# EEG_Preprocessing.net
KiCad netlist of a schematic drawn in Altium Designer
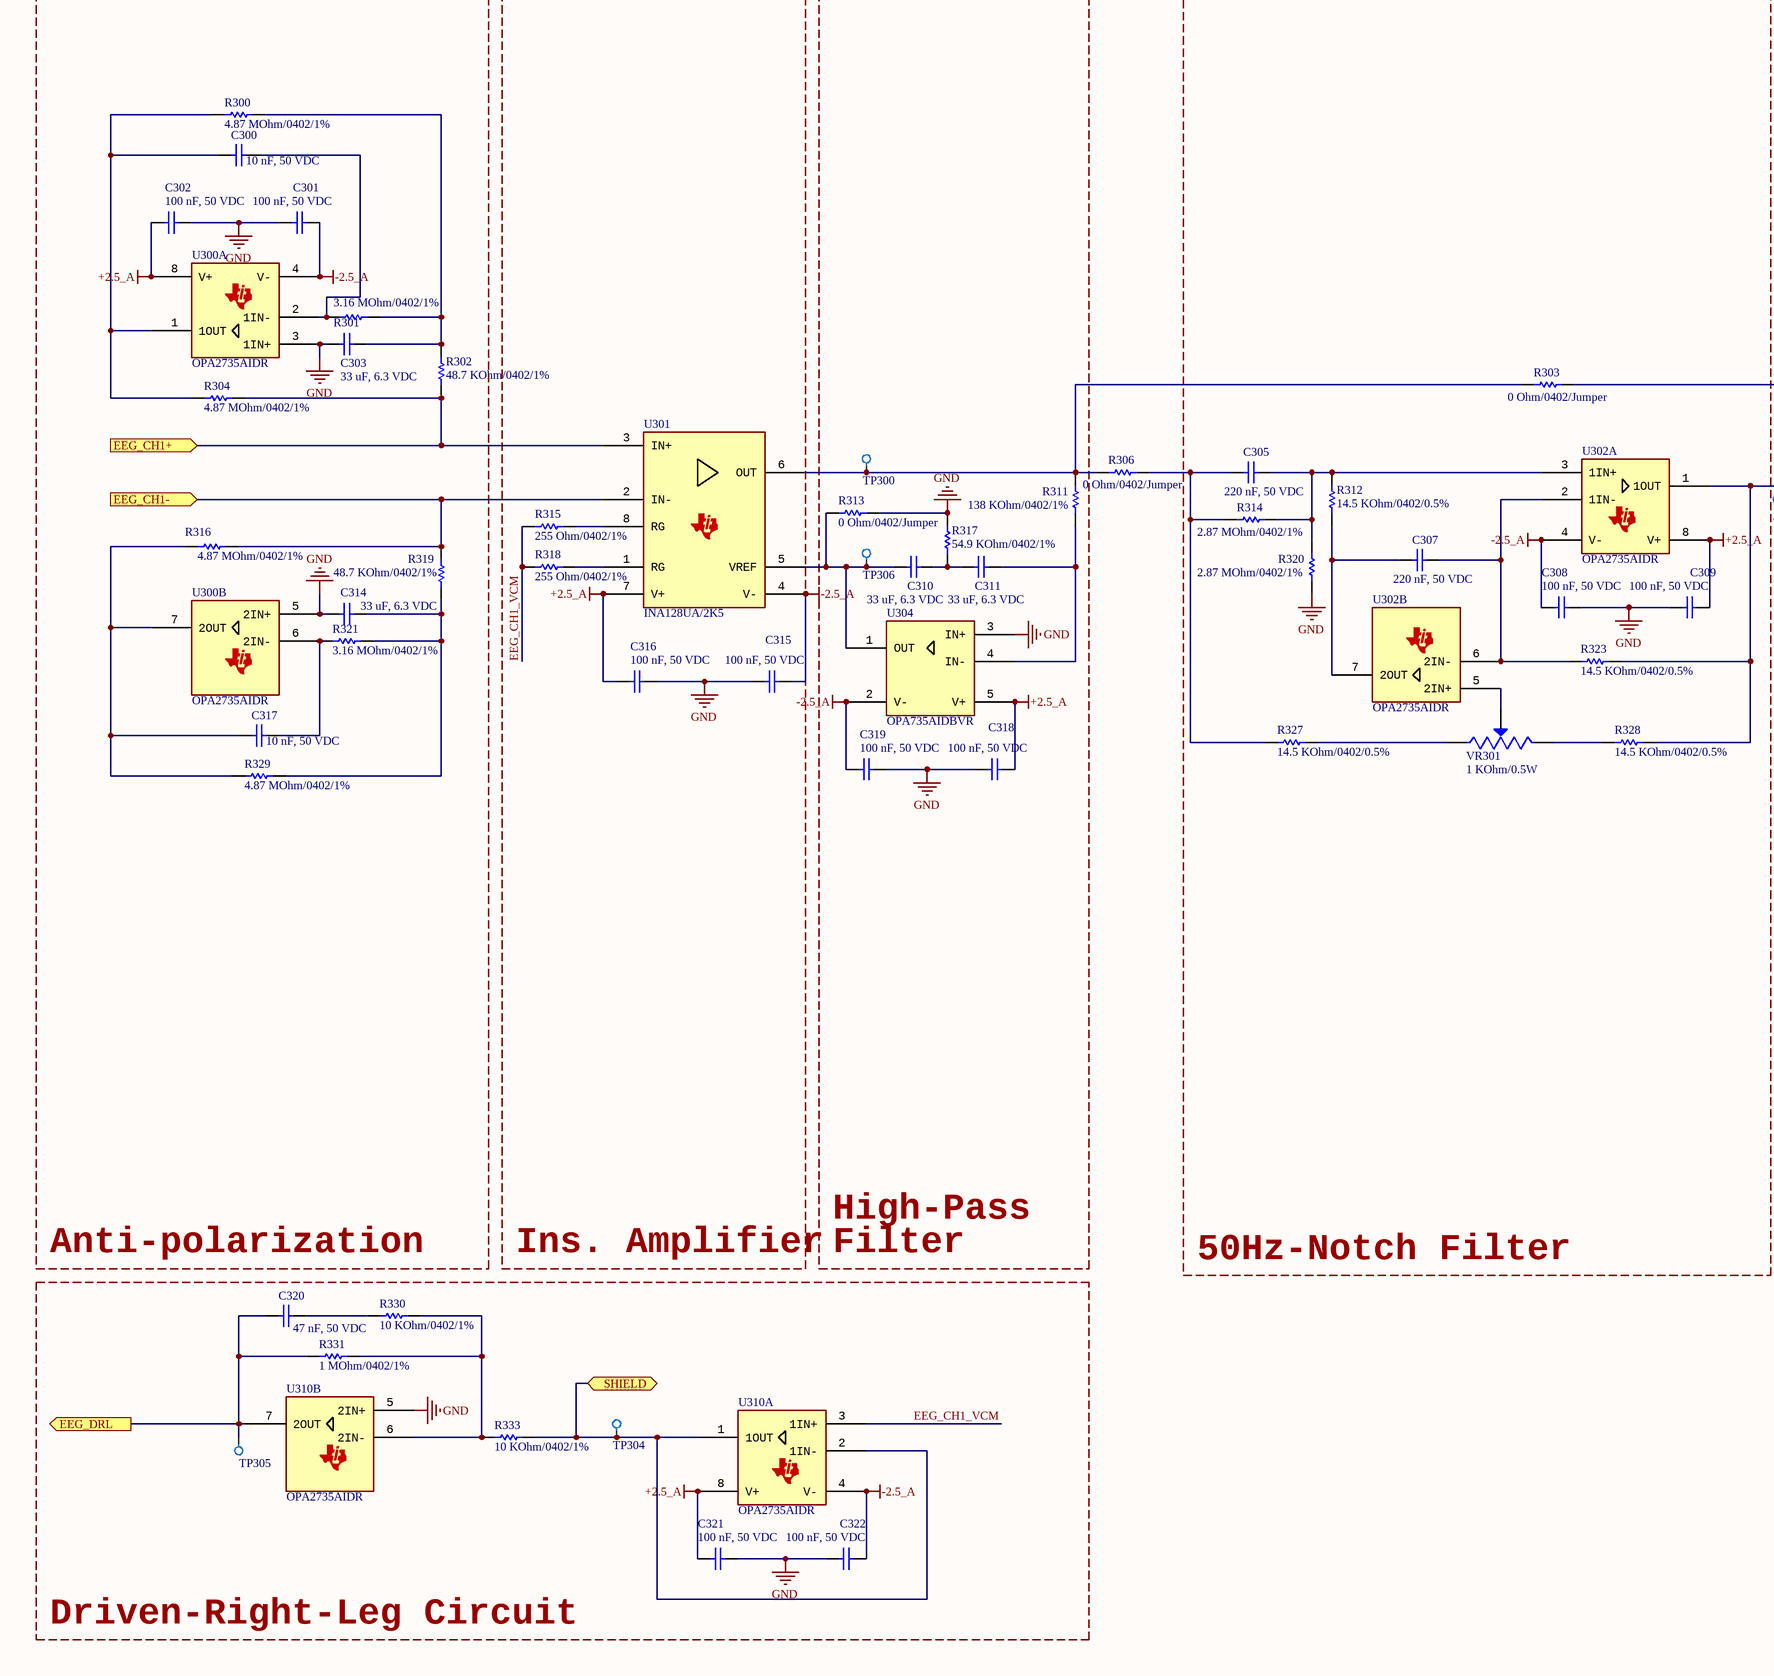
[diagram p0: EEG Preprocessing.SchDoc, left]
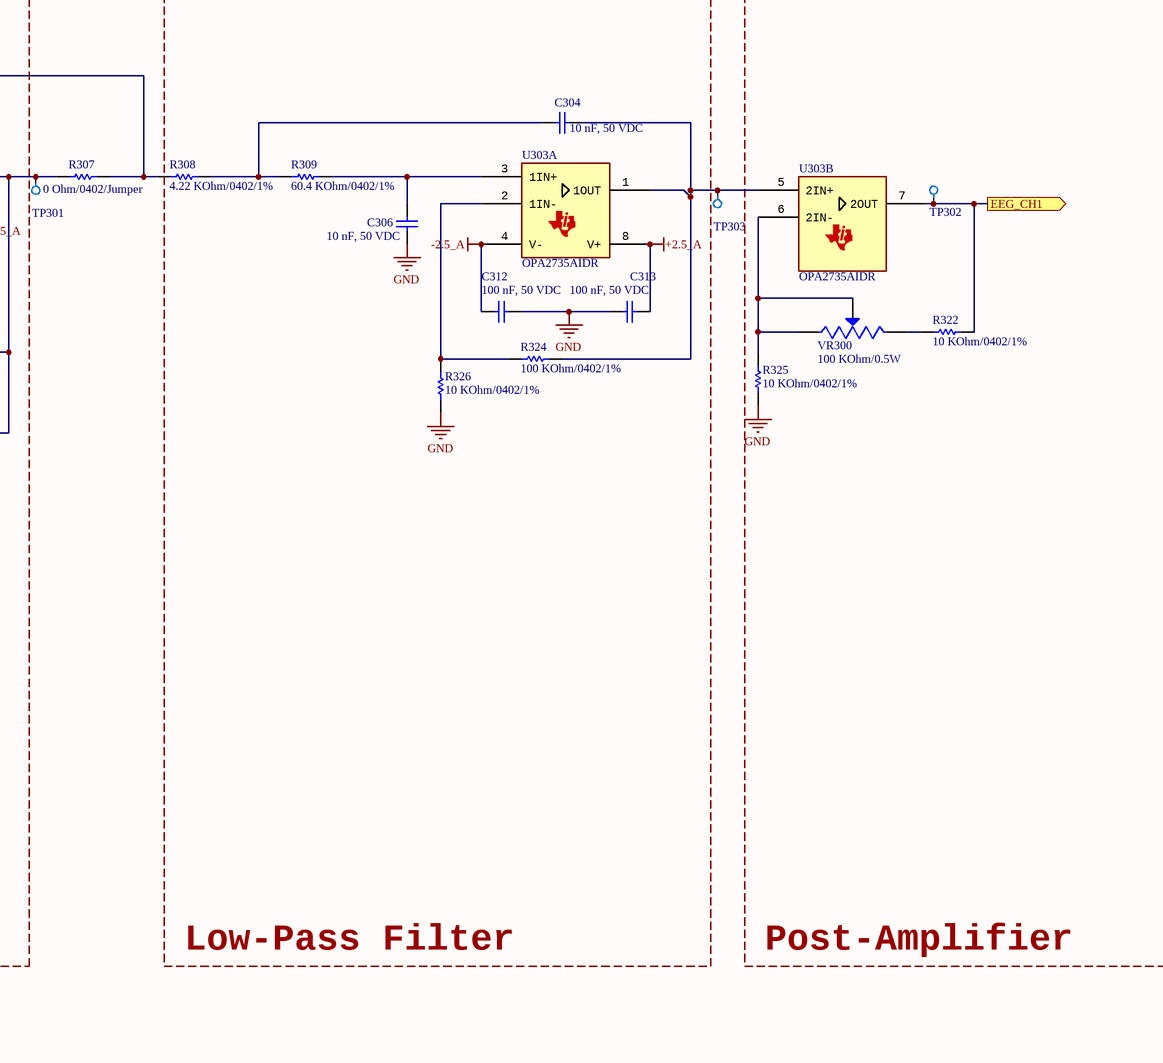
[diagram p1: EEG Preprocessing.SchDoc, right]

(export (version "E")
  (design (tool "Eeschema 10.0.6"))
  (components
    (comp (ref "C300")
      (value "10 nF, 50 VDC")
      (footprint "CAP_0603")
      (description "CAP, size 0603, 10 nF, 50 VDC")
      (fields (field (name "TOLERANCE") "+/-5%"))
      (libsource (lib "Altium_Ceramic_Cap") (part "0106031030550"))
    )
    (comp (ref "C301")
      (value "100 nF, 50 VDC")
      (footprint "CAP_0603")
      (description "CAP, size 0603, 100 nF, 50 VDC")
      (fields (field (name "TOLERANCE") "+/-10%"))
      (libsource (lib "Altium_Ceramic_Cap") (part "0106031041050"))
    )
    (comp (ref "C302")
      (value "100 nF, 50 VDC")
      (footprint "CAP_0603")
      (description "CAP, size 0603, 100 nF, 50 VDC")
      (fields (field (name "TOLERANCE") "+/-10%"))
      (libsource (lib "Altium_Ceramic_Cap") (part "0106031041050"))
    )
    (comp (ref "C303")
      (value "33 uF, 6.3 VDC")
      (footprint "CAP_0805")
      (description "33 µF ±20% 6.3V Ceramic Capacitor X5R 0805 (2012 Metric)")
      (fields (field (name "TOLERANCE") "+/-10%"))
      (libsource (lib "Altium_Ceramic_Cap") (part "0108051061025"))
    )
    (comp (ref "C304")
      (value "10 nF, 50 VDC")
      (footprint "CAP_0603")
      (description "CAP, size 0603, 10 nF, 50 VDC")
      (fields (field (name "TOLERANCE") "+/-5%"))
      (libsource (lib "Altium_Ceramic_Cap") (part "0106031030550"))
    )
    (comp (ref "C305")
      (value "220 nF, 50 VDC")
      (footprint "CAP_0603")
      (description "CAP, size 0603, 220 nF, 50 VDC")
      (fields (field (name "TOLERANCE") "+/-10%"))
      (libsource (lib "Altium_Ceramic_Cap") (part "0106032241050"))
    )
    (comp (ref "C306")
      (value "10 nF, 50 VDC")
      (footprint "CAP_0603")
      (description "CAP, size 0603, 10 nF, 50 VDC")
      (fields (field (name "TOLERANCE") "+/-5%"))
      (libsource (lib "Altium_Ceramic_Cap") (part "0106031030550"))
    )
    (comp (ref "C307")
      (value "220 nF, 50 VDC")
      (footprint "CAP_0603")
      (description "CAP, size 0603, 220 nF, 50 VDC")
      (fields (field (name "TOLERANCE") "+/-10%"))
      (libsource (lib "Altium_Ceramic_Cap") (part "0106032241050"))
    )
    (comp (ref "C308")
      (value "100 nF, 50 VDC")
      (footprint "CAP_0603")
      (description "CAP, size 0603, 100 nF, 50 VDC")
      (fields (field (name "TOLERANCE") "+/-10%"))
      (libsource (lib "Altium_Ceramic_Cap") (part "0106031041050"))
    )
    (comp (ref "C309")
      (value "100 nF, 50 VDC")
      (footprint "CAP_0603")
      (description "CAP, size 0603, 100 nF, 50 VDC")
      (fields (field (name "TOLERANCE") "+/-10%"))
      (libsource (lib "Altium_Ceramic_Cap") (part "0106031041050"))
    )
    (comp (ref "C310")
      (value "33 uF, 6.3 VDC")
      (footprint "CAP_0805")
      (description "33 µF ±20% 6.3V Ceramic Capacitor X5R 0805 (2012 Metric)")
      (fields (field (name "TOLERANCE") "+/-10%"))
      (libsource (lib "Altium_Ceramic_Cap") (part "0108051061025"))
    )
    (comp (ref "C311")
      (value "33 uF, 6.3 VDC")
      (footprint "CAP_0805")
      (description "33 µF ±20% 6.3V Ceramic Capacitor X5R 0805 (2012 Metric)")
      (fields (field (name "TOLERANCE") "+/-10%"))
      (libsource (lib "Altium_Ceramic_Cap") (part "0108051061025"))
    )
    (comp (ref "C312")
      (value "100 nF, 50 VDC")
      (footprint "CAP_0603")
      (description "CAP, size 0603, 100 nF, 50 VDC")
      (fields (field (name "TOLERANCE") "+/-10%"))
      (libsource (lib "Altium_Ceramic_Cap") (part "0106031041050"))
    )
    (comp (ref "C313")
      (value "100 nF, 50 VDC")
      (footprint "CAP_0603")
      (description "CAP, size 0603, 100 nF, 50 VDC")
      (fields (field (name "TOLERANCE") "+/-10%"))
      (libsource (lib "Altium_Ceramic_Cap") (part "0106031041050"))
    )
    (comp (ref "C314")
      (value "33 uF, 6.3 VDC")
      (footprint "CAP_0805")
      (description "33 µF ±20% 6.3V Ceramic Capacitor X5R 0805 (2012 Metric)")
      (fields (field (name "TOLERANCE") "+/-10%"))
      (libsource (lib "Altium_Ceramic_Cap") (part "0108051061025"))
    )
    (comp (ref "C315")
      (value "100 nF, 50 VDC")
      (footprint "CAP_0603")
      (description "CAP, size 0603, 100 nF, 50 VDC")
      (fields (field (name "TOLERANCE") "+/-10%"))
      (libsource (lib "Altium_Ceramic_Cap") (part "0106031041050"))
    )
    (comp (ref "C316")
      (value "100 nF, 50 VDC")
      (footprint "CAP_0603")
      (description "CAP, size 0603, 100 nF, 50 VDC")
      (fields (field (name "TOLERANCE") "+/-10%"))
      (libsource (lib "Altium_Ceramic_Cap") (part "0106031041050"))
    )
    (comp (ref "C317")
      (value "10 nF, 50 VDC")
      (footprint "CAP_0603")
      (description "CAP, size 0603, 10 nF, 50 VDC")
      (fields (field (name "TOLERANCE") "+/-5%"))
      (libsource (lib "Altium_Ceramic_Cap") (part "0106031030550"))
    )
    (comp (ref "C318")
      (value "100 nF, 50 VDC")
      (footprint "CAP_0603")
      (description "CAP, size 0603, 100 nF, 50 VDC")
      (fields (field (name "TOLERANCE") "+/-10%"))
      (libsource (lib "Altium_Ceramic_Cap") (part "0106031041050"))
    )
    (comp (ref "C319")
      (value "100 nF, 50 VDC")
      (footprint "CAP_0603")
      (description "CAP, size 0603, 100 nF, 50 VDC")
      (fields (field (name "TOLERANCE") "+/-10%"))
      (libsource (lib "Altium_Ceramic_Cap") (part "0106031041050"))
    )
    (comp (ref "C320")
      (value "47 nF, 50 VDC")
      (footprint "CAP_0603")
      (description "CAP, size 0603, 47 nF, 50 VDC")
      (fields (field (name "TOLERANCE") "+/-10%"))
      (libsource (lib "Altium_Ceramic_Cap") (part "0106034731050"))
    )
    (comp (ref "C321")
      (value "100 nF, 50 VDC")
      (footprint "CAP_0603")
      (description "CAP, size 0603, 100 nF, 50 VDC")
      (fields (field (name "TOLERANCE") "+/-10%"))
      (libsource (lib "Altium_Ceramic_Cap") (part "0106031041050"))
    )
    (comp (ref "C322")
      (value "100 nF, 50 VDC")
      (footprint "CAP_0603")
      (description "CAP, size 0603, 100 nF, 50 VDC")
      (fields (field (name "TOLERANCE") "+/-10%"))
      (libsource (lib "Altium_Ceramic_Cap") (part "0106031041050"))
    )
    (comp (ref "R300")
      (value "4.87 MOhm/0402/1%")
      (footprint "R0402")
      (description "4.87 MOhms ±1% 0.063W, 1/16W Chip Resistor 0402 (1005 Metric) Moisture Resistant Thick Film")
      (fields (field (name "Comment") "Resistor 4.87 MOhm 0402 1%"))
      (libsource (lib "Giang_Resistor") (part "Resistor 4.87 MOhm 0402 1%"))
    )
    (comp (ref "R301")
      (value "3.16 MOhm/0402/1%")
      (footprint "R0402")
      (description "3.16 MOhms ±1% 0.063W, 1/16W Chip Resistor 0402 (1005 Metric) Automotive AEC-Q200 Thick Film")
      (fields (field (name "Comment") "Resistor 3.16 MOhm 0402 1%"))
      (libsource (lib "Giang_Resistor") (part "Resistor 3.16 MOhm 0402 1%"))
    )
    (comp (ref "R302")
      (value "48.7 KOhm/0402/1%")
      (footprint "R0402")
      (fields (field (name "Comment") "Resistor 48.7 KOhm 0402 1%"))
      (libsource (lib "Giang_Resistor") (part "Resistor 48.7 KOhm 0402 1%"))
    )
    (comp (ref "R303")
      (value "0 Ohm/0402/Jumper")
      (footprint "R0402")
      (description "0 Ohms Jumper Chip Resistor 0402 (1005 Metric) Moisture Resistant Thick Film")
      (fields (field (name "Comment") "Resistor 0 Ohm 0402"))
      (libsource (lib "Giang_Resistor") (part "Resistor 0 Ohm 0402"))
    )
    (comp (ref "R304")
      (value "4.87 MOhm/0402/1%")
      (footprint "R0402")
      (description "4.87 MOhms ±1% 0.063W, 1/16W Chip Resistor 0402 (1005 Metric) Moisture Resistant Thick Film")
      (fields (field (name "Comment") "Resistor 4.87 MOhm 0402 1%"))
      (libsource (lib "Giang_Resistor") (part "Resistor 4.87 MOhm 0402 1%"))
    )
    (comp (ref "R306")
      (value "0 Ohm/0402/Jumper")
      (footprint "R0402")
      (description "0 Ohms Jumper Chip Resistor 0402 (1005 Metric) Moisture Resistant Thick Film")
      (fields (field (name "Comment") "Resistor 0 Ohm 0402"))
      (libsource (lib "Giang_Resistor") (part "Resistor 0 Ohm 0402"))
    )
    (comp (ref "R307")
      (value "0 Ohm/0402/Jumper")
      (footprint "R0402")
      (description "0 Ohms Jumper Chip Resistor 0402 (1005 Metric) Moisture Resistant Thick Film")
      (fields (field (name "Comment") "Resistor 0 Ohm 0402"))
      (libsource (lib "Giang_Resistor") (part "Resistor 0 Ohm 0402"))
    )
    (comp (ref "R308")
      (value "4.22 KOhm/0402/1%")
      (footprint "R0402")
      (description "4.22 kOhms ±1% 0.1W, 1/10W Chip Resistor 0402 (1005 Metric) Automotive AEC-Q200 Thick Film")
      (fields (field (name "Comment") "Resistor 4.22 KOhm 0402 1%"))
      (libsource (lib "Giang_Resistor") (part "Resistor 4.22 KOhm 0402 1%"))
    )
    (comp (ref "R309")
      (value "60.4 KOhm/0402/1%")
      (footprint "R0402")
      (description "60.4 kOhms ±1% 0.063W, 1/16W Chip Resistor 0402 (1005 Metric) Moisture Resistant Thick Film")
      (fields (field (name "Comment") "Resistor 60.4 KOhm 0402 1%"))
      (libsource (lib "Giang_Resistor") (part "Resistor 60.4 KOhm 0402 1%"))
    )
    (comp (ref "R311")
      (value "138 KOhm/0402/1%")
      (footprint "R0402")
      (fields (field (name "Comment") "Resistor 138 KOhm 0402 1%"))
      (libsource (lib "Giang_Resistor") (part "Resistor 138 KOhm 0402 1%"))
    )
    (comp (ref "R312")
      (value "14.5 KOhm/0402/0.5%")
      (footprint "R0402")
      (description "14.5 kOhms ±0.5% 0.063W, 1/16W Chip Resistor 0402 (1005 Metric) Thin Film")
      (fields (field (name "Comment") "Resistor 14.5 KOhm 0402 0.5%"))
      (libsource (lib "Giang_Resistor") (part "Resistor 14.5 KOhm 0402 0.5%"))
    )
    (comp (ref "R313")
      (value "0 Ohm/0402/Jumper")
      (footprint "R0402")
      (description "0 Ohms Jumper Chip Resistor 0402 (1005 Metric) Moisture Resistant Thick Film")
      (fields (field (name "Comment") "Resistor 0 Ohm 0402"))
      (libsource (lib "Giang_Resistor") (part "Resistor 0 Ohm 0402"))
    )
    (comp (ref "R314")
      (value "2.87 MOhm/0402/1%")
      (footprint "R0402")
      (description "2.87 MOhms ±1% 0.063W, 1/16W Chip Resistor 0402 (1005 Metric) Automotive AEC-Q200 Thick Film")
      (fields (field (name "Comment") "Resistor 2.87 MOhm 0402 1%"))
      (libsource (lib "Giang_Resistor") (part "Resistor 2.87 MOhm 0402 1%"))
    )
    (comp (ref "R315")
      (value "255 Ohm/0402/1%")
      (footprint "R0402")
      (description "255 Ohms ±1% 0.1W, 1/10W Chip Resistor 0402 (1005 Metric) Automotive AEC-Q200 Thick Film")
      (fields (field (name "Comment") "Resistor 255 Ohm 0402 1%"))
      (libsource (lib "Giang_Resistor") (part "Resistor 255 Ohm 0402 1%"))
    )
    (comp (ref "R316")
      (value "4.87 MOhm/0402/1%")
      (footprint "R0402")
      (description "4.87 MOhms ±1% 0.063W, 1/16W Chip Resistor 0402 (1005 Metric) Moisture Resistant Thick Film")
      (fields (field (name "Comment") "Resistor 4.87 MOhm 0402 1%"))
      (libsource (lib "Giang_Resistor") (part "Resistor 4.87 MOhm 0402 1%"))
    )
    (comp (ref "R317")
      (value "54.9 KOhm/0402/1%")
      (footprint "R0402")
      (fields (field (name "Comment") "Resistor 54.9 KOhm 0402 1%"))
      (libsource (lib "Giang_Resistor") (part "Resistor 54.9 KOhm 0402 1%"))
    )
    (comp (ref "R318")
      (value "255 Ohm/0402/1%")
      (footprint "R0402")
      (description "255 Ohms ±1% 0.1W, 1/10W Chip Resistor 0402 (1005 Metric) Automotive AEC-Q200 Thick Film")
      (fields (field (name "Comment") "Resistor 255 Ohm 0402 1%"))
      (libsource (lib "Giang_Resistor") (part "Resistor 255 Ohm 0402 1%"))
    )
    (comp (ref "R319")
      (value "48.7 KOhm/0402/1%")
      (footprint "R0402")
      (fields (field (name "Comment") "Resistor 48.7 KOhm 0402 1%"))
      (libsource (lib "Giang_Resistor") (part "Resistor 48.7 KOhm 0402 1%"))
    )
    (comp (ref "R320")
      (value "2.87 MOhm/0402/1%")
      (footprint "R0402")
      (description "2.87 MOhms ±1% 0.063W, 1/16W Chip Resistor 0402 (1005 Metric) Automotive AEC-Q200 Thick Film")
      (fields (field (name "Comment") "Resistor 2.87 MOhm 0402 1%"))
      (libsource (lib "Giang_Resistor") (part "Resistor 2.87 MOhm 0402 1%"))
    )
    (comp (ref "R321")
      (value "3.16 MOhm/0402/1%")
      (footprint "R0402")
      (description "3.16 MOhms ±1% 0.063W, 1/16W Chip Resistor 0402 (1005 Metric) Automotive AEC-Q200 Thick Film")
      (fields (field (name "Comment") "Resistor 3.16 MOhm 0402 1%"))
      (libsource (lib "Giang_Resistor") (part "Resistor 3.16 MOhm 0402 1%"))
    )
    (comp (ref "R322")
      (value "10 KOhm/0402/1%")
      (footprint "R0402")
      (description "Code 103, 1/16W 1%")
      (fields (field (name "Comment") "Resistor 10 KOhm 0402 1%"))
      (libsource (lib "Giang_Resistor") (part "Resistor 10 KOhm 0402 1%"))
    )
    (comp (ref "R323")
      (value "14.5 KOhm/0402/0.5%")
      (footprint "R0402")
      (description "14.5 kOhms ±0.5% 0.063W, 1/16W Chip Resistor 0402 (1005 Metric) Thin Film")
      (fields (field (name "Comment") "Resistor 14.5 KOhm 0402 0.5%"))
      (libsource (lib "Giang_Resistor") (part "Resistor 14.5 KOhm 0402 0.5%"))
    )
    (comp (ref "R324")
      (value "100 KOhm/0402/1%")
      (footprint "R0402")
      (description "Code 104, 1/16W 1%")
      (fields (field (name "Comment") "Resistor 100 KOhm 0402 1%"))
      (libsource (lib "Giang_Resistor") (part "Resistor 100 KOhm 0402 1%"))
    )
    (comp (ref "R325")
      (value "10 KOhm/0402/1%")
      (footprint "R0402")
      (description "Code 103, 1/16W 1%")
      (fields (field (name "Comment") "Resistor 10 KOhm 0402 1%"))
      (libsource (lib "Giang_Resistor") (part "Resistor 10 KOhm 0402 1%"))
    )
    (comp (ref "R326")
      (value "10 KOhm/0402/1%")
      (footprint "R0402")
      (description "Code 103, 1/16W 1%")
      (fields (field (name "Comment") "Resistor 10 KOhm 0402 1%"))
      (libsource (lib "Giang_Resistor") (part "Resistor 10 KOhm 0402 1%"))
    )
    (comp (ref "R327")
      (value "14.5 KOhm/0402/0.5%")
      (footprint "R0402")
      (description "14.5 kOhms ±0.5% 0.063W, 1/16W Chip Resistor 0402 (1005 Metric) Thin Film")
      (fields (field (name "Comment") "Resistor 14.5 KOhm 0402 0.5%"))
      (libsource (lib "Giang_Resistor") (part "Resistor 14.5 KOhm 0402 0.5%"))
    )
    (comp (ref "R328")
      (value "14.5 KOhm/0402/0.5%")
      (footprint "R0402")
      (description "14.5 kOhms ±0.5% 0.063W, 1/16W Chip Resistor 0402 (1005 Metric) Thin Film")
      (fields (field (name "Comment") "Resistor 14.5 KOhm 0402 0.5%"))
      (libsource (lib "Giang_Resistor") (part "Resistor 14.5 KOhm 0402 0.5%"))
    )
    (comp (ref "R329")
      (value "4.87 MOhm/0402/1%")
      (footprint "R0402")
      (description "4.87 MOhms ±1% 0.063W, 1/16W Chip Resistor 0402 (1005 Metric) Moisture Resistant Thick Film")
      (fields (field (name "Comment") "Resistor 4.87 MOhm 0402 1%"))
      (libsource (lib "Giang_Resistor") (part "Resistor 4.87 MOhm 0402 1%"))
    )
    (comp (ref "R330")
      (value "10 KOhm/0402/1%")
      (footprint "R0402")
      (description "Code 103, 1/16W 1%")
      (fields (field (name "Comment") "Resistor 10 KOhm 0402 1%"))
      (libsource (lib "Giang_Resistor") (part "Resistor 10 KOhm 0402 1%"))
    )
    (comp (ref "R331")
      (value "1 MOhm/0402/1%")
      (footprint "R0402")
      (description "Code 105, 1/16W 1%")
      (fields (field (name "Comment") "Resistor 1 MOhm 0402 1%_1"))
      (libsource (lib "Giang_Resistor") (part "Resistor 1 MOhm 0402 1%_1"))
    )
    (comp (ref "R333")
      (value "10 KOhm/0402/1%")
      (footprint "R0402")
      (description "Code 103, 1/16W 1%")
      (fields (field (name "Comment") "Resistor 10 KOhm 0402 1%"))
      (libsource (lib "Giang_Resistor") (part "Resistor 10 KOhm 0402 1%"))
    )
    (comp (ref "TP300")
      (value "Testpoint_TH")
      (footprint "TestPoint_THTPad_D1.5mm_Drill0.7mm")
      (description "Test Point TEST-1BK")
      (libsource (lib "BluetoothTracking") (part "Testpoint_TH"))
    )
    (comp (ref "TP301")
      (value "Testpoint_TH")
      (footprint "TestPoint_THTPad_D1.5mm_Drill0.7mm")
      (description "Test Point TEST-1BK")
      (libsource (lib "BluetoothTracking") (part "Testpoint_TH"))
    )
    (comp (ref "TP302")
      (value "Testpoint_TH")
      (footprint "TestPoint_THTPad_D1.5mm_Drill0.7mm")
      (description "Test Point TEST-1BK")
      (libsource (lib "BluetoothTracking") (part "Testpoint_TH"))
    )
    (comp (ref "TP303")
      (value "Testpoint_TH")
      (footprint "TestPoint_THTPad_D1.5mm_Drill0.7mm")
      (description "Test Point TEST-1BK")
      (libsource (lib "BluetoothTracking") (part "Testpoint_TH"))
    )
    (comp (ref "TP304")
      (value "Testpoint_TH")
      (footprint "TestPoint_THTPad_D1.5mm_Drill0.7mm")
      (description "Test Point TEST-1BK")
      (libsource (lib "BluetoothTracking") (part "Testpoint_TH"))
    )
    (comp (ref "TP305")
      (value "Testpoint_TH")
      (footprint "TestPoint_THTPad_D1.5mm_Drill0.7mm")
      (description "Test Point TEST-1BK")
      (libsource (lib "BluetoothTracking") (part "Testpoint_TH"))
    )
    (comp (ref "TP306")
      (value "Testpoint_TH")
      (footprint "TestPoint_THTPad_D1.5mm_Drill0.7mm")
      (description "Test Point TEST-1BK")
      (libsource (lib "BluetoothTracking") (part "Testpoint_TH"))
    )
    (comp (ref "U300")
      (value "OPA2735AIDR")
      (footprint "SOIC-8")
      (description "0.05μV/°C max, Single-Supply CMOS Operational Amplifiers Zero-drift Series")
      (libsource (lib "") (part "OPA2735AIDR_1"))
    )
    (comp (ref "U301")
      (value "INA128UA/2K5")
      (footprint "SOIC-8")
      (description "Precision, Low Power Instrumentation Amplifiers")
      (libsource (lib "Giang_Amplifiers") (part "INA128UA/2K5"))
    )
    (comp (ref "U302")
      (value "OPA2735AIDR")
      (footprint "SOIC-8")
      (description "0.05μV/°C max, Single-Supply CMOS Operational Amplifiers Zero-drift Series")
      (libsource (lib "Giang_Amplifiers") (part "OPA2735AIDR"))
    )
    (comp (ref "U303")
      (value "OPA2735AIDR")
      (footprint "SOIC-8")
      (description "0.05μV/°C max, Single-Supply CMOS Operational Amplifiers Zero-drift Series")
      (libsource (lib "Giang_Amplifiers") (part "OPA2735AIDR"))
    )
    (comp (ref "U304")
      (value "OPA735AIDBVR")
      (footprint "SOT-23")
      (description "Zero-Drift Amplifier 1 Circuit Rail-to-Rail SOT-23-5")
      (libsource (lib "Giang_Amplifiers") (part "OPA735AIDBVR"))
    )
    (comp (ref "U310")
      (value "OPA2735AIDR")
      (footprint "SOIC-8")
      (description "0.05μV/°C max, Single-Supply CMOS Operational Amplifiers Zero-drift Series")
      (libsource (lib "") (part "OPA2735AIDR_1"))
    )
    (comp (ref "VR300")
      (value "100 KOhm/0.5W")
      (footprint "TRIM_3296W")
      (description "100 KOhms 0.5W, PC Pins Through Hole Trimmer Potentiometer Cermet 25.0 Turn Top Adjustment")
      (fields (field (name "MF") "Bourns") (field (name "MP") "3296W-1-250"))
      (libsource (lib "Giang_Potentionmeter") (part "3296W-104"))
    )
    (comp (ref "VR301")
      (value "1 KOhm/0.5W")
      (footprint "TRIM_3296W")
      (description "1 KOhms 0.5W, PC Pins Through Hole Trimmer Potentiometer Cermet 25.0 Turn Top Adjustment")
      (fields (field (name "Comment") "3296W-102"))
      (libsource (lib "Giang_Potentionmeter") (part "3296W-102"))
    )
  )
  (nets
    (net (code "1") (name "+2.5_A") (class "Default")
      (node (ref "C302") (pin "2") (pinfunction "2_2") (pintype "passive"))
      (node (ref "C309") (pin "1") (pinfunction "1_1") (pintype "passive"))
      (node (ref "C313") (pin "1") (pinfunction "1_1") (pintype "passive"))
      (node (ref "C316") (pin "2") (pinfunction "2_2") (pintype "passive"))
      (node (ref "C318") (pin "1") (pinfunction "1_1") (pintype "passive"))
      (node (ref "C321") (pin "2") (pinfunction "2_2") (pintype "passive"))
      (node (ref "U300") (pin "8") (pinfunction "V+_8") (pintype "passive"))
      (node (ref "U301") (pin "7") (pinfunction "V+_7") (pintype "passive"))
      (node (ref "U302") (pin "8") (pinfunction "V+_8") (pintype "passive"))
      (node (ref "U303") (pin "8") (pinfunction "V+_8") (pintype "passive"))
      (node (ref "U304") (pin "5") (pinfunction "V+_5") (pintype "passive"))
      (node (ref "U310") (pin "8") (pinfunction "V+_8") (pintype "passive"))
    )
    (net (code "2") (name "-2.5_A") (class "Default")
      (node (ref "C301") (pin "1") (pinfunction "1_1") (pintype "passive"))
      (node (ref "C308") (pin "2") (pinfunction "2_2") (pintype "passive"))
      (node (ref "C312") (pin "2") (pinfunction "2_2") (pintype "passive"))
      (node (ref "C315") (pin "1") (pinfunction "1_1") (pintype "passive"))
      (node (ref "C319") (pin "2") (pinfunction "2_2") (pintype "passive"))
      (node (ref "C322") (pin "1") (pinfunction "1_1") (pintype "passive"))
      (node (ref "U300") (pin "4") (pinfunction "V-_4") (pintype "passive"))
      (node (ref "U301") (pin "4") (pinfunction "V-_4") (pintype "passive"))
      (node (ref "U302") (pin "4") (pinfunction "V-_4") (pintype "passive"))
      (node (ref "U303") (pin "4") (pinfunction "V-_4") (pintype "passive"))
      (node (ref "U304") (pin "2") (pinfunction "V-_2") (pintype "passive"))
      (node (ref "U310") (pin "4") (pinfunction "V-_4") (pintype "passive"))
    )
    (net (code "3") (name "/EEG_CH1") (class "Default")
      (node (ref "R322") (pin "1") (pinfunction "1_1") (pintype "passive"))
      (node (ref "TP302") (pin "1") (pinfunction "1_1") (pintype "passive"))
      (node (ref "U303") (pin "7") (pinfunction "2OUT_7") (pintype "passive"))
    )
    (net (code "4") (name "/EEG_CH1+") (class "Default")
      (node (ref "R302") (pin "1") (pinfunction "1_1") (pintype "passive"))
      (node (ref "R304") (pin "2") (pinfunction "2_2") (pintype "passive"))
      (node (ref "U301") (pin "3") (pinfunction "IN+_3") (pintype "passive"))
    )
    (net (code "5") (name "/EEG_CH1-") (class "Default")
      (node (ref "R316") (pin "2") (pinfunction "2_2") (pintype "passive"))
      (node (ref "R319") (pin "2") (pinfunction "2_2") (pintype "passive"))
      (node (ref "U301") (pin "2") (pinfunction "IN-_2") (pintype "passive"))
    )
    (net (code "6") (name "/EEG_CH1_VCM") (class "Default")
      (node (ref "R315") (pin "2") (pinfunction "2_2") (pintype "passive"))
      (node (ref "R318") (pin "2") (pinfunction "2_2") (pintype "passive"))
      (node (ref "U310") (pin "3") (pinfunction "1IN+_3") (pintype "passive"))
    )
    (net (code "7") (name "/EEG_DRL") (class "Default")
      (node (ref "C320") (pin "1") (pinfunction "1_1") (pintype "passive"))
      (node (ref "R331") (pin "1") (pinfunction "1_1") (pintype "passive"))
      (node (ref "TP305") (pin "1") (pinfunction "1_1") (pintype "passive"))
      (node (ref "U310") (pin "7") (pinfunction "2OUT_7") (pintype "passive"))
    )
    (net (code "8") (name "/SHIELD") (class "Default")
      (node (ref "R333") (pin "2") (pinfunction "2_2") (pintype "passive"))
      (node (ref "TP304") (pin "1") (pinfunction "1_1") (pintype "passive"))
      (node (ref "U310") (pin "1") (pinfunction "1OUT_1") (pintype "passive"))
      (node (ref "U310") (pin "2") (pinfunction "1IN-_2") (pintype "passive"))
    )
    (net (code "9") (name "GND") (class "Default")
      (node (ref "C301") (pin "2") (pinfunction "2_2") (pintype "passive"))
      (node (ref "C302") (pin "1") (pinfunction "1_1") (pintype "passive"))
      (node (ref "C303") (pin "1") (pinfunction "1_1") (pintype "passive"))
      (node (ref "C306") (pin "1") (pinfunction "1_1") (pintype "passive"))
      (node (ref "C308") (pin "1") (pinfunction "1_1") (pintype "passive"))
      (node (ref "C309") (pin "2") (pinfunction "2_2") (pintype "passive"))
      (node (ref "C312") (pin "1") (pinfunction "1_1") (pintype "passive"))
      (node (ref "C313") (pin "2") (pinfunction "2_2") (pintype "passive"))
      (node (ref "C314") (pin "1") (pinfunction "1_1") (pintype "passive"))
      (node (ref "C315") (pin "2") (pinfunction "2_2") (pintype "passive"))
      (node (ref "C316") (pin "1") (pinfunction "1_1") (pintype "passive"))
      (node (ref "C318") (pin "2") (pinfunction "2_2") (pintype "passive"))
      (node (ref "C319") (pin "1") (pinfunction "1_1") (pintype "passive"))
      (node (ref "C321") (pin "1") (pinfunction "1_1") (pintype "passive"))
      (node (ref "C322") (pin "2") (pinfunction "2_2") (pintype "passive"))
      (node (ref "R313") (pin "1") (pinfunction "1_1") (pintype "passive"))
      (node (ref "R317") (pin "1") (pinfunction "1_1") (pintype "passive"))
      (node (ref "R320") (pin "1") (pinfunction "1_1") (pintype "passive"))
      (node (ref "R325") (pin "1") (pinfunction "1_1") (pintype "passive"))
      (node (ref "R326") (pin "1") (pinfunction "1_1") (pintype "passive"))
      (node (ref "U300") (pin "3") (pinfunction "1IN+_3") (pintype "passive"))
      (node (ref "U300") (pin "5") (pinfunction "2IN+_5") (pintype "passive"))
      (node (ref "U304") (pin "3") (pinfunction "IN+_3") (pintype "passive"))
      (node (ref "U310") (pin "5") (pinfunction "2IN+_5") (pintype "passive"))
    )
    (net (code "10") (name "Net-(C303-Pad2)") (class "Default")
      (node (ref "C303") (pin "2") (pinfunction "2_2") (pintype "passive"))
      (node (ref "R300") (pin "2") (pinfunction "2_2") (pintype "passive"))
      (node (ref "R301") (pin "2") (pinfunction "2_2") (pintype "passive"))
      (node (ref "R302") (pin "2") (pinfunction "2_2") (pintype "passive"))
    )
    (net (code "11") (name "Net-(C304-Pad1)") (class "Default")
      (node (ref "C304") (pin "1") (pinfunction "1_1") (pintype "passive"))
      (node (ref "R308") (pin "2") (pinfunction "2_2") (pintype "passive"))
      (node (ref "R309") (pin "1") (pinfunction "1_1") (pintype "passive"))
    )
    (net (code "12") (name "Net-(C305-Pad1)") (class "Default")
      (node (ref "C305") (pin "1") (pinfunction "1_1") (pintype "passive"))
      (node (ref "R306") (pin "2") (pinfunction "2_2") (pintype "passive"))
      (node (ref "R314") (pin "1") (pinfunction "1_1") (pintype "passive"))
      (node (ref "R327") (pin "2") (pinfunction "2_2") (pintype "passive"))
    )
    (net (code "13") (name "Net-(C310-Pad2)") (class "Default")
      (node (ref "C310") (pin "2") (pinfunction "2_2") (pintype "passive"))
      (node (ref "C311") (pin "1") (pinfunction "1_1") (pintype "passive"))
      (node (ref "R317") (pin "2") (pinfunction "2_2") (pintype "passive"))
    )
    (net (code "14") (name "Net-(C314-Pad2)") (class "Default")
      (node (ref "C314") (pin "2") (pinfunction "2_2") (pintype "passive"))
      (node (ref "R319") (pin "1") (pinfunction "1_1") (pintype "passive"))
      (node (ref "R321") (pin "2") (pinfunction "2_2") (pintype "passive"))
      (node (ref "R329") (pin "2") (pinfunction "2_2") (pintype "passive"))
    )
    (net (code "15") (name "Net-(C320-Pad2)") (class "Default")
      (node (ref "C320") (pin "2") (pinfunction "2_2") (pintype "passive"))
      (node (ref "R330") (pin "1") (pinfunction "1_1") (pintype "passive"))
    )
    (net (code "16") (name "Net-(R303-Pad2)") (class "Default")
      (node (ref "R303") (pin "2") (pinfunction "2_2") (pintype "passive"))
      (node (ref "R307") (pin "2") (pinfunction "2_2") (pintype "passive"))
      (node (ref "R308") (pin "1") (pinfunction "1_1") (pintype "passive"))
    )
    (net (code "17") (name "Net-(R315-Pad1)") (class "Default")
      (node (ref "R315") (pin "1") (pinfunction "1_1") (pintype "passive"))
      (node (ref "U301") (pin "8") (pinfunction "RG_8") (pintype "passive"))
    )
    (net (code "18") (name "Net-(R318-Pad1)") (class "Default")
      (node (ref "R318") (pin "1") (pinfunction "1_1") (pintype "passive"))
      (node (ref "U301") (pin "1") (pinfunction "RG_1") (pintype "passive"))
    )
    (net (code "19") (name "Net-(U300A-1IN-)") (class "Default")
      (node (ref "C300") (pin "2") (pinfunction "2_2") (pintype "passive"))
      (node (ref "R301") (pin "1") (pinfunction "1_1") (pintype "passive"))
      (node (ref "U300") (pin "2") (pinfunction "1IN-_2") (pintype "passive"))
    )
    (net (code "20") (name "Net-(U300A-1OUT)") (class "Default")
      (node (ref "C300") (pin "1") (pinfunction "1_1") (pintype "passive"))
      (node (ref "R300") (pin "1") (pinfunction "1_1") (pintype "passive"))
      (node (ref "R304") (pin "1") (pinfunction "1_1") (pintype "passive"))
      (node (ref "U300") (pin "1") (pinfunction "1OUT_1") (pintype "passive"))
    )
    (net (code "21") (name "Net-(U300B-2IN-)") (class "Default")
      (node (ref "C317") (pin "2") (pinfunction "2_2") (pintype "passive"))
      (node (ref "R321") (pin "1") (pinfunction "1_1") (pintype "passive"))
      (node (ref "U300") (pin "6") (pinfunction "2IN-_6") (pintype "passive"))
    )
    (net (code "22") (name "Net-(U300B-2OUT)") (class "Default")
      (node (ref "C317") (pin "1") (pinfunction "1_1") (pintype "passive"))
      (node (ref "R316") (pin "1") (pinfunction "1_1") (pintype "passive"))
      (node (ref "R329") (pin "1") (pinfunction "1_1") (pintype "passive"))
      (node (ref "U300") (pin "7") (pinfunction "2OUT_7") (pintype "passive"))
    )
    (net (code "23") (name "Net-(U301-OUT)") (class "Default")
      (node (ref "R303") (pin "1") (pinfunction "1_1") (pintype "passive"))
      (node (ref "R306") (pin "1") (pinfunction "1_1") (pintype "passive"))
      (node (ref "R311") (pin "2") (pinfunction "2_2") (pintype "passive"))
      (node (ref "TP300") (pin "1") (pinfunction "1_1") (pintype "passive"))
      (node (ref "U301") (pin "6") (pinfunction "OUT_6") (pintype "passive"))
    )
    (net (code "24") (name "Net-(U301-VREF)") (class "Default")
      (node (ref "C310") (pin "1") (pinfunction "1_1") (pintype "passive"))
      (node (ref "R313") (pin "2") (pinfunction "2_2") (pintype "passive"))
      (node (ref "TP306") (pin "1") (pinfunction "1_1") (pintype "passive"))
      (node (ref "U301") (pin "5") (pinfunction "VREF_5") (pintype "passive"))
      (node (ref "U304") (pin "1") (pinfunction "OUT_1") (pintype "passive"))
    )
    (net (code "25") (name "Net-(U302A-1IN+)") (class "Default")
      (node (ref "C305") (pin "2") (pinfunction "2_2") (pintype "passive"))
      (node (ref "R312") (pin "2") (pinfunction "2_2") (pintype "passive"))
      (node (ref "R314") (pin "2") (pinfunction "2_2") (pintype "passive"))
      (node (ref "R320") (pin "2") (pinfunction "2_2") (pintype "passive"))
      (node (ref "U302") (pin "3") (pinfunction "1IN+_3") (pintype "passive"))
    )
    (net (code "26") (name "Net-(U302A-1IN-)") (class "Default")
      (node (ref "C307") (pin "2") (pinfunction "2_2") (pintype "passive"))
      (node (ref "R323") (pin "2") (pinfunction "2_2") (pintype "passive"))
      (node (ref "U302") (pin "2") (pinfunction "1IN-_2") (pintype "passive"))
      (node (ref "U302") (pin "6") (pinfunction "2IN-_6") (pintype "passive"))
    )
    (net (code "27") (name "Net-(U302A-1OUT)") (class "Default")
      (node (ref "R307") (pin "1") (pinfunction "1_1") (pintype "passive"))
      (node (ref "R323") (pin "1") (pinfunction "1_1") (pintype "passive"))
      (node (ref "R328") (pin "1") (pinfunction "1_1") (pintype "passive"))
      (node (ref "TP301") (pin "1") (pinfunction "1_1") (pintype "passive"))
      (node (ref "U302") (pin "1") (pinfunction "1OUT_1") (pintype "passive"))
    )
    (net (code "28") (name "Net-(U302B-2IN+)") (class "Default")
      (node (ref "U302") (pin "5") (pinfunction "2IN+_5") (pintype "passive"))
      (node (ref "VR301") (pin "2") (pinfunction "WIPER_2") (pintype "passive"))
    )
    (net (code "29") (name "Net-(U302B-2OUT)") (class "Default")
      (node (ref "C307") (pin "1") (pinfunction "1_1") (pintype "passive"))
      (node (ref "R312") (pin "1") (pinfunction "1_1") (pintype "passive"))
      (node (ref "U302") (pin "7") (pinfunction "2OUT_7") (pintype "passive"))
    )
    (net (code "30") (name "Net-(U303A-1IN+)") (class "Default")
      (node (ref "C306") (pin "2") (pinfunction "2_2") (pintype "passive"))
      (node (ref "R309") (pin "2") (pinfunction "2_2") (pintype "passive"))
      (node (ref "U303") (pin "3") (pinfunction "1IN+_3") (pintype "passive"))
    )
    (net (code "31") (name "Net-(U303A-1IN-)") (class "Default")
      (node (ref "R324") (pin "1") (pinfunction "1_1") (pintype "passive"))
      (node (ref "R326") (pin "2") (pinfunction "2_2") (pintype "passive"))
      (node (ref "U303") (pin "2") (pinfunction "1IN-_2") (pintype "passive"))
    )
    (net (code "32") (name "Net-(U303A-1OUT)") (class "Default")
      (node (ref "C304") (pin "2") (pinfunction "2_2") (pintype "passive"))
      (node (ref "R324") (pin "2") (pinfunction "2_2") (pintype "passive"))
      (node (ref "TP303") (pin "1") (pinfunction "1_1") (pintype "passive"))
      (node (ref "U303") (pin "1") (pinfunction "1OUT_1") (pintype "passive"))
      (node (ref "U303") (pin "5") (pinfunction "2IN+_5") (pintype "passive"))
    )
    (net (code "33") (name "Net-(U303B-2IN-)") (class "Default")
      (node (ref "R325") (pin "2") (pinfunction "2_2") (pintype "passive"))
      (node (ref "U303") (pin "6") (pinfunction "2IN-_6") (pintype "passive"))
      (node (ref "VR300") (pin "1") (pinfunction "CCW_1") (pintype "passive"))
      (node (ref "VR300") (pin "2") (pinfunction "WIPER_2") (pintype "passive"))
    )
    (net (code "34") (name "Net-(U304-IN-)") (class "Default")
      (node (ref "C311") (pin "2") (pinfunction "2_2") (pintype "passive"))
      (node (ref "R311") (pin "1") (pinfunction "1_1") (pintype "passive"))
      (node (ref "U304") (pin "4") (pinfunction "IN-_4") (pintype "passive"))
    )
    (net (code "35") (name "Net-(U310B-2IN-)") (class "Default")
      (node (ref "R330") (pin "2") (pinfunction "2_2") (pintype "passive"))
      (node (ref "R331") (pin "2") (pinfunction "2_2") (pintype "passive"))
      (node (ref "R333") (pin "1") (pinfunction "1_1") (pintype "passive"))
      (node (ref "U310") (pin "6") (pinfunction "2IN-_6") (pintype "passive"))
    )
    (net (code "36") (name "Net-(VR300-CW)") (class "Default")
      (node (ref "R322") (pin "2") (pinfunction "2_2") (pintype "passive"))
      (node (ref "VR300") (pin "3") (pinfunction "CW_3") (pintype "passive"))
    )
    (net (code "37") (name "Net-(VR301-CCW)") (class "Default")
      (node (ref "R327") (pin "1") (pinfunction "1_1") (pintype "passive"))
      (node (ref "VR301") (pin "1") (pinfunction "CCW_1") (pintype "passive"))
    )
    (net (code "38") (name "Net-(VR301-CW)") (class "Default")
      (node (ref "R328") (pin "2") (pinfunction "2_2") (pintype "passive"))
      (node (ref "VR301") (pin "3") (pinfunction "CW_3") (pintype "passive"))
    )
  )
)
